# 02_ldo5v5.net
KiCad netlist of a schematic drawn in Altium Designer
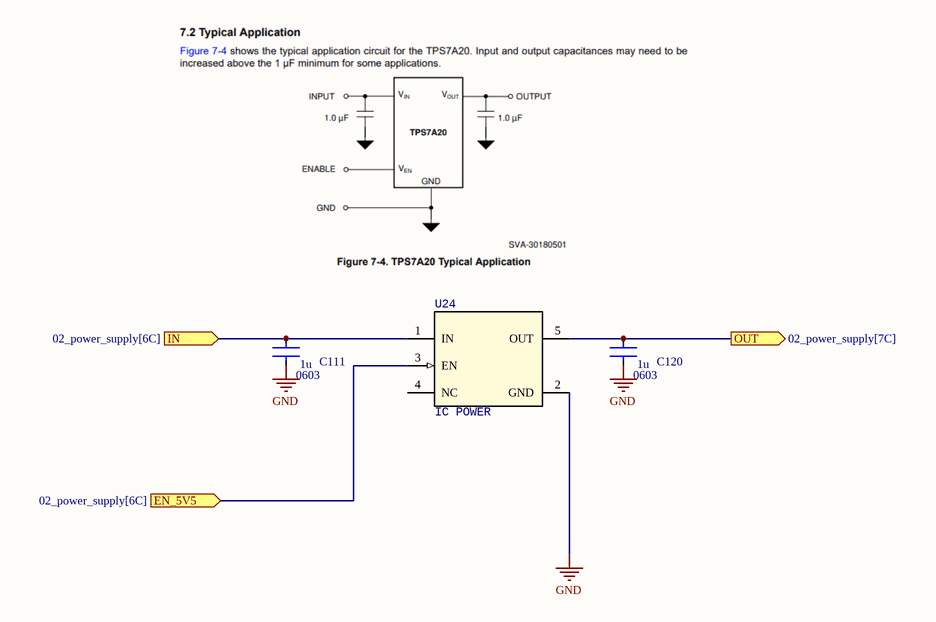
[diagram p0: 02_ldo5v5.SchDoc]

(export (version "E")
  (design (tool "Eeschema 10.0.6"))
  (components
    (comp (ref "C111")
      (value "C1608X5R1E105K080AC")
      (footprint "CAPTDK0603")
      (description "CAP CER 1UF 25V X5R 0603")
      (libsource (lib "tcspc00") (part "C1608X5R1E105K080AC"))
    )
    (comp (ref "C120")
      (value "C1608X5R1E105K080AC")
      (footprint "CAPTDK0603")
      (description "CAP CER 1UF 25V X5R 0603")
      (libsource (lib "tcspc00") (part "C1608X5R1E105K080AC"))
    )
    (comp (ref "U24")
      (value "IC POWER")
      (footprint "SOT-23-5")
      (description "Linear Voltage Regulator IC Positive Fixed 1 Output 300mA SOT-23-5 5v5")
      (libsource (lib "tcspc00") (part "TPS7A2055PDBVR"))
    )
  )
  (nets
    (net (code "1") (name "/EN_5V5") (class "Default")
      (node (ref "U24") (pin "3") (pinfunction "EN_3") (pintype "input"))
    )
    (net (code "2") (name "/IN") (class "Default")
      (node (ref "C111") (pin "1") (pinfunction "1_1") (pintype "passive"))
      (node (ref "U24") (pin "1") (pinfunction "IN_1") (pintype "power_in"))
    )
    (net (code "3") (name "/OUT") (class "Default")
      (node (ref "C120") (pin "1") (pinfunction "1_1") (pintype "passive"))
      (node (ref "U24") (pin "5") (pinfunction "OUT_5") (pintype "passive"))
    )
    (net (code "4") (name "GND") (class "Default")
      (node (ref "C111") (pin "2") (pinfunction "2_2") (pintype "passive"))
      (node (ref "C120") (pin "2") (pinfunction "2_2") (pintype "passive"))
      (node (ref "U24") (pin "2") (pinfunction "GND_2") (pintype "power_in"))
    )
    (net (code "5") (name "unconnected-(U24-NC-Pad4)") (class "Default")
      (node (ref "U24") (pin "4") (pinfunction "NC_4") (pintype "passive"))
    )
  )
)
